# Upper_Board.net
KiCad netlist of a schematic drawn in EAGLE
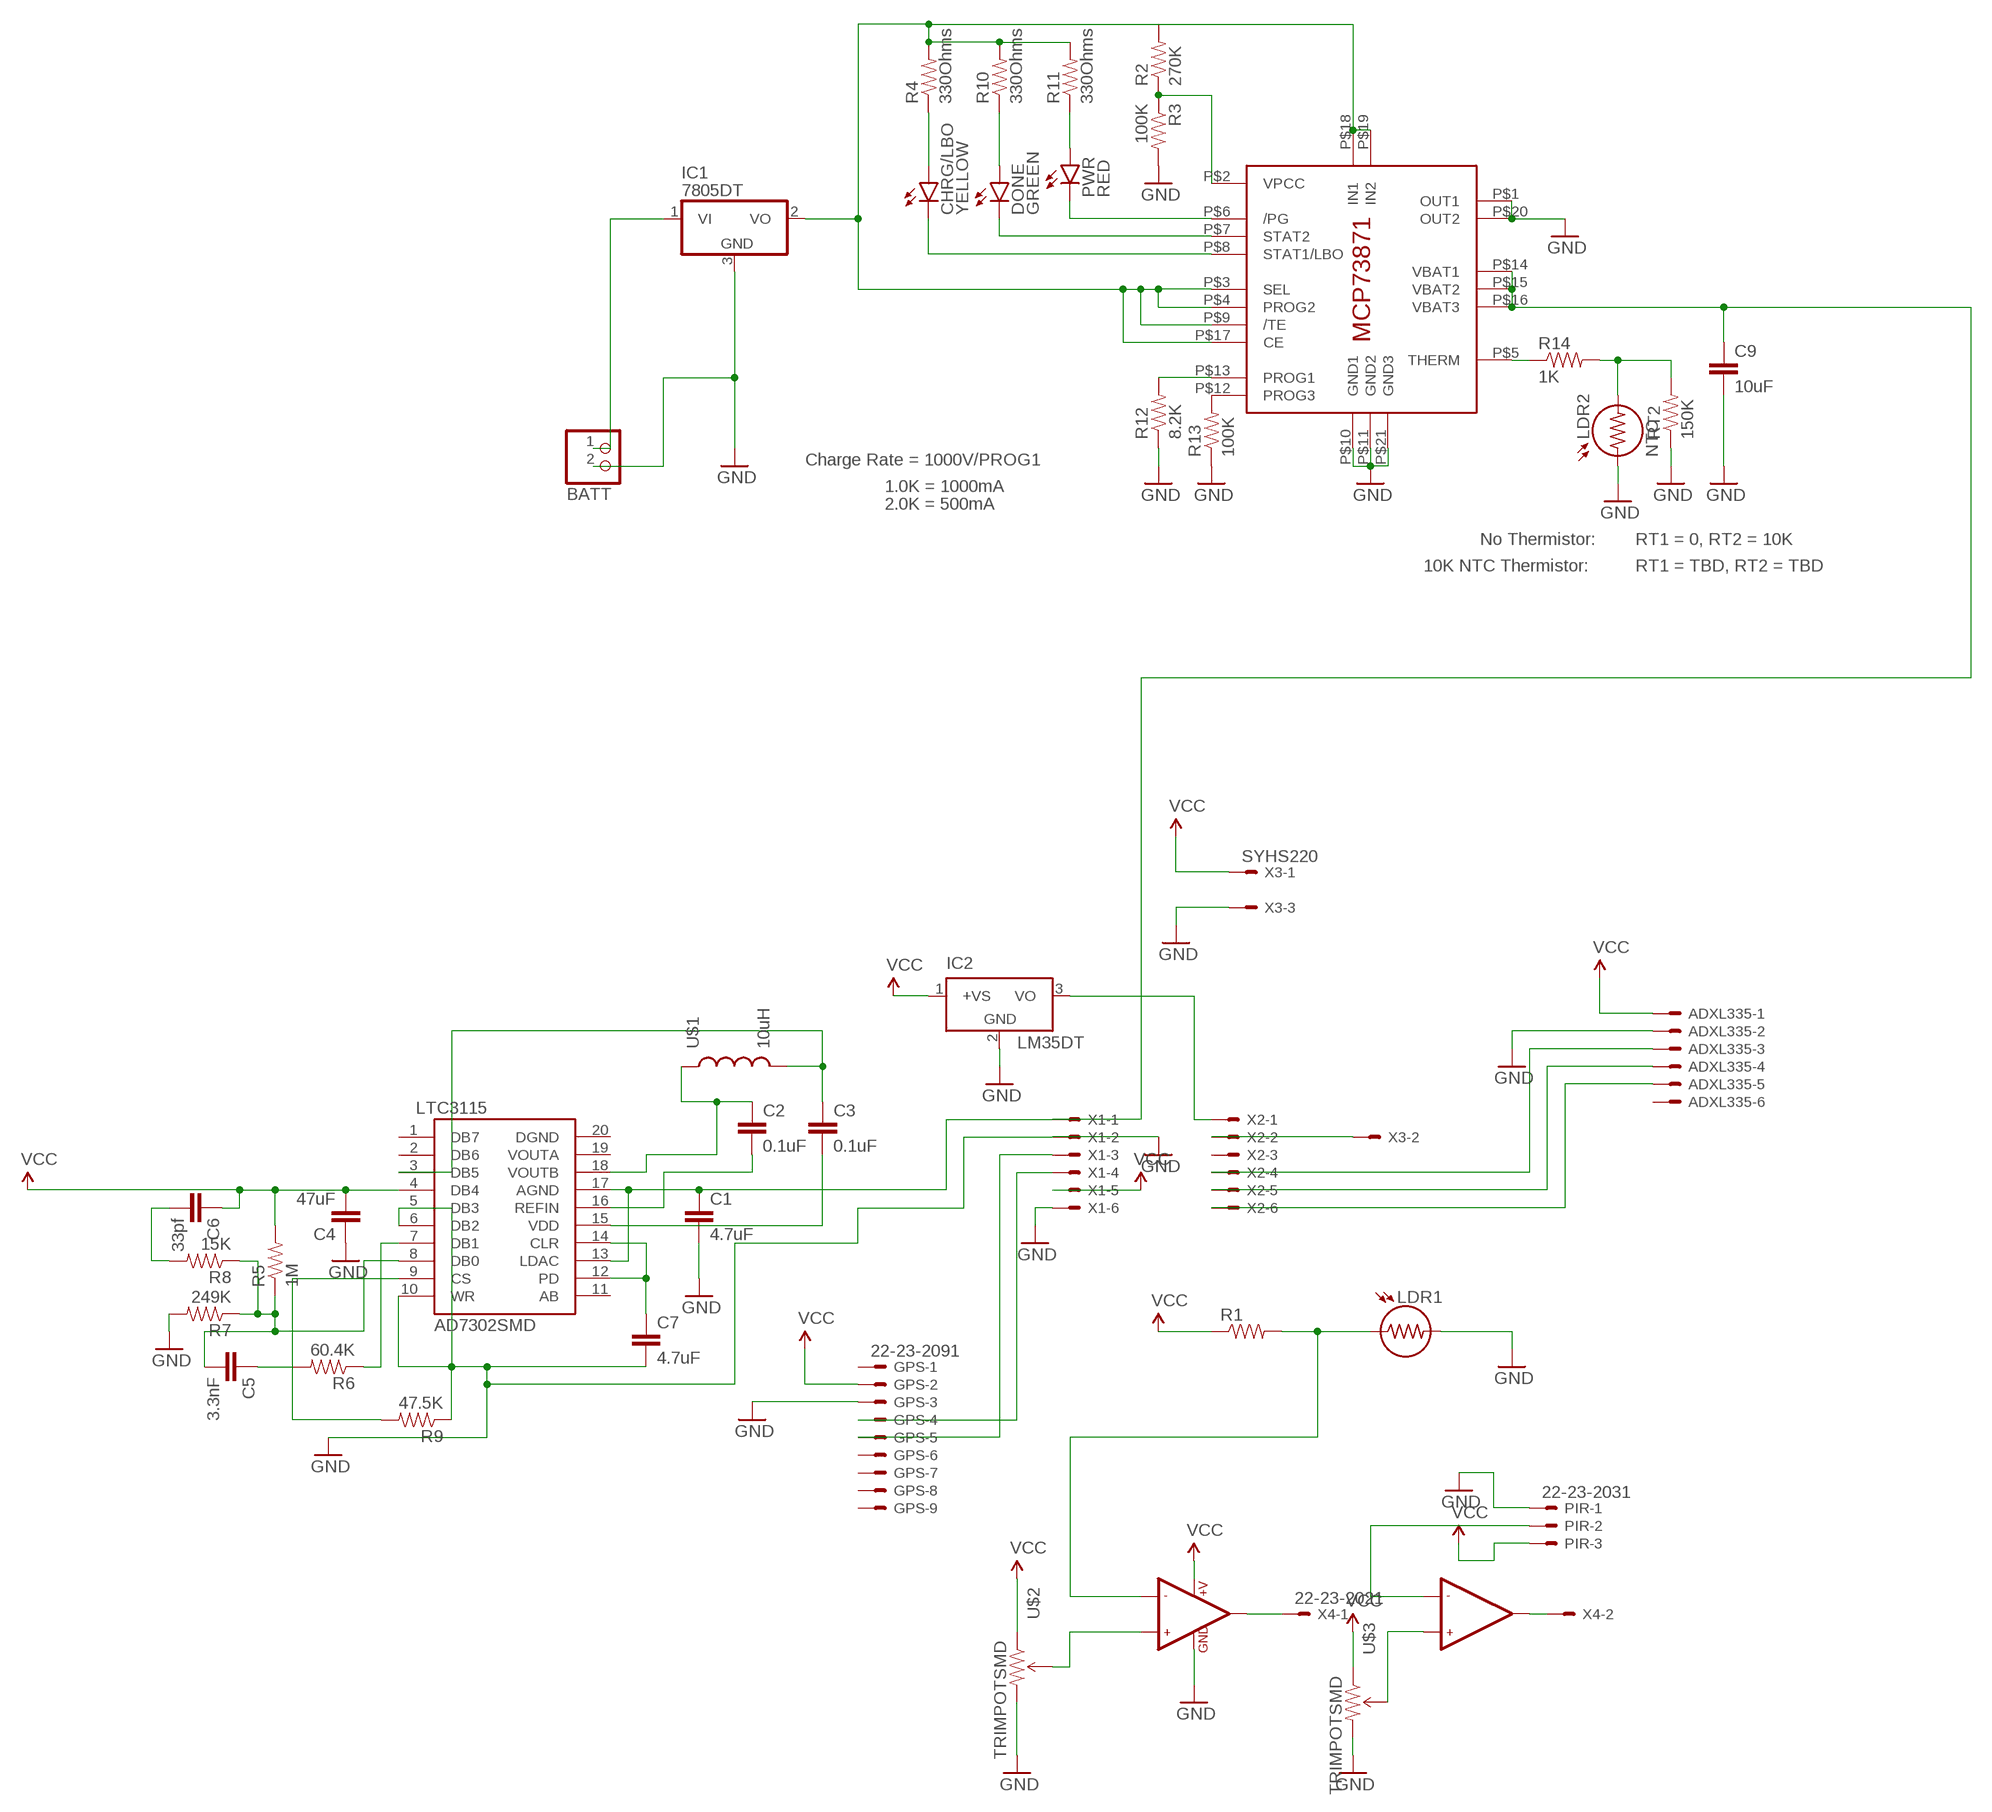
[diagram p0: schematic, sheet 1]

(export (version "E")
  (design (tool "Eeschema 10.0.6"))
  (components
    (comp (ref "ADXL335")
      (value "22-23-2061")
      (footprint "eagle-import:22-23-2061")
      (fields (field (name "MF") "MOLEX"))
      (libsource (lib "eagle-import") (part "22-23-2061"))
    )
    (comp (ref "BATT")
      (value "JST_2PIN-SMT-RA")
      (footprint "eagle-import:JST-PH-2-SMT-RA")
      (libsource (lib "eagle-import") (part "JST_2PIN-SMT-RA"))
    )
    (comp (ref "C1")
      (value "4.7uF")
      (footprint "eagle-import:0603-CAP")
      (libsource (lib "eagle-import") (part "CAP0603-CAP"))
    )
    (comp (ref "C2")
      (value "0.1uF")
      (footprint "eagle-import:0603-CAP")
      (libsource (lib "eagle-import") (part "CAP0603-CAP"))
    )
    (comp (ref "C3")
      (value "0.1uF")
      (footprint "eagle-import:0603-CAP")
      (libsource (lib "eagle-import") (part "CAP0603-CAP"))
    )
    (comp (ref "C4")
      (value "47uF")
      (footprint "eagle-import:0603-CAP")
      (libsource (lib "eagle-import") (part "CAP0603-CAP"))
    )
    (comp (ref "C5")
      (value "3.3nF")
      (footprint "eagle-import:0603-CAP")
      (libsource (lib "eagle-import") (part "CAP0603-CAP"))
    )
    (comp (ref "C6")
      (value "33pf")
      (footprint "eagle-import:0603-CAP")
      (libsource (lib "eagle-import") (part "CAP0603-CAP"))
    )
    (comp (ref "C7")
      (value "4.7uF")
      (footprint "eagle-import:0603-CAP")
      (libsource (lib "eagle-import") (part "CAP0603-CAP"))
    )
    (comp (ref "C9")
      (value "10uF")
      (footprint "eagle-import:0603-CAP")
      (libsource (lib "eagle-import") (part "CAP0603-CAP"))
    )
    (comp (ref "CHRG/LBO")
      (value "YELLOW")
      (footprint "eagle-import:LED-1206")
      (libsource (lib "eagle-import") (part "LED-YELLOWLARGE"))
    )
    (comp (ref "DONE")
      (value "GREEN")
      (footprint "eagle-import:LED-1206")
      (libsource (lib "eagle-import") (part "LED-GREENLARGE"))
    )
    (comp (ref "GPS")
      (value "22-23-2091")
      (footprint "eagle-import:22-23-2091")
      (fields (field (name "MF") "MOLEX"))
      (libsource (lib "eagle-import") (part "22-23-2091"))
    )
    (comp (ref "IC1")
      (value "7805DT")
      (footprint "eagle-import:TO252")
      (libsource (lib "eagle-import") (part "78DT05"))
    )
    (comp (ref "IC2")
      (value "LM35DT")
      (footprint "eagle-import:TO220V")
      (libsource (lib "eagle-import") (part "LM35DT"))
    )
    (comp (ref "IC4")
      (value "MCP73871")
      (footprint "eagle-import:QFN20_4MM")
      (libsource (lib "eagle-import") (part "MCP73871"))
    )
    (comp (ref "LDR1")
      (value "LDR5MM")
      (footprint "eagle-import:LDR338-54C")
      (libsource (lib "eagle-import") (part "LDR5MM"))
    )
    (comp (ref "LDR2")
      (value "NTC")
      (footprint "eagle-import:LDR338-54C")
      (libsource (lib "eagle-import") (part "LDR5MM"))
    )
    (comp (ref "LTC3115")
      (value "AD7302SMD")
      (footprint "eagle-import:TSSOP20")
      (libsource (lib "eagle-import") (part "AD7302SMD"))
    )
    (comp (ref "PIR")
      (value "22-23-2031")
      (footprint "eagle-import:22-23-2031")
      (fields (field (name "MF") "MOLEX"))
      (libsource (lib "eagle-import") (part "22-23-2031"))
    )
    (comp (ref "PWR")
      (value "RED")
      (footprint "eagle-import:LED-1206")
      (libsource (lib "eagle-import") (part "LED-RED1206"))
    )
    (comp (ref "R1")
      (value "RESISTOR1206")
      (footprint "eagle-import:1206")
      (libsource (lib "eagle-import") (part "RESISTOR1206"))
    )
    (comp (ref "R2")
      (value "270K")
      (footprint "eagle-import:1206")
      (libsource (lib "eagle-import") (part "RESISTOR1206"))
    )
    (comp (ref "R3")
      (value "100K")
      (footprint "eagle-import:1206")
      (libsource (lib "eagle-import") (part "RESISTOR1206"))
    )
    (comp (ref "R4")
      (value "330Ohms")
      (footprint "eagle-import:1206")
      (libsource (lib "eagle-import") (part "RESISTOR1206"))
    )
    (comp (ref "R5")
      (value "1M")
      (footprint "eagle-import:1206")
      (libsource (lib "eagle-import") (part "RESISTOR1206"))
    )
    (comp (ref "R6")
      (value "60.4K")
      (footprint "eagle-import:1206")
      (libsource (lib "eagle-import") (part "RESISTOR1206"))
    )
    (comp (ref "R7")
      (value "249K")
      (footprint "eagle-import:1206")
      (libsource (lib "eagle-import") (part "RESISTOR1206"))
    )
    (comp (ref "R8")
      (value "15K")
      (footprint "eagle-import:1206")
      (libsource (lib "eagle-import") (part "RESISTOR1206"))
    )
    (comp (ref "R9")
      (value "47.5K")
      (footprint "eagle-import:1206")
      (libsource (lib "eagle-import") (part "RESISTOR1206"))
    )
    (comp (ref "R10")
      (value "330Ohms")
      (footprint "eagle-import:1206")
      (libsource (lib "eagle-import") (part "RESISTOR1206"))
    )
    (comp (ref "R11")
      (value "330Ohms")
      (footprint "eagle-import:1206")
      (libsource (lib "eagle-import") (part "RESISTOR1206"))
    )
    (comp (ref "R12")
      (value "8.2K")
      (footprint "eagle-import:1206")
      (libsource (lib "eagle-import") (part "RESISTOR1206"))
    )
    (comp (ref "R13")
      (value "100K")
      (footprint "eagle-import:1206")
      (libsource (lib "eagle-import") (part "RESISTOR1206"))
    )
    (comp (ref "R14")
      (value "1K")
      (footprint "eagle-import:1206")
      (libsource (lib "eagle-import") (part "RESISTOR1206"))
    )
    (comp (ref "RT2")
      (value "150K")
      (footprint "eagle-import:1206")
      (libsource (lib "eagle-import") (part "RESISTOR1206"))
    )
    (comp (ref "U$1")
      (value "10uH")
      (footprint "eagle-import:INDUCTOR-1206")
      (libsource (lib "eagle-import") (part "INDUCTORH1206"))
    )
    (comp (ref "U$2")
      (value "TRIMPOTSMD")
      (footprint "eagle-import:TRIMPOT-3MM")
      (libsource (lib "eagle-import") (part "TRIMPOTSMD"))
    )
    (comp (ref "U$3")
      (value "TRIMPOTSMD")
      (footprint "eagle-import:TRIMPOT-3MM")
      (libsource (lib "eagle-import") (part "TRIMPOTSMD"))
    )
    (comp (ref "U$4")
      (value "LMV358")
      (footprint "eagle-import:SO08")
      (libsource (lib "eagle-import") (part "LMV358"))
    )
    (comp (ref "X1")
      (value "22-23-2061")
      (footprint "eagle-import:22-23-2061")
      (fields (field (name "MF") "MOLEX"))
      (libsource (lib "eagle-import") (part "22-23-2061"))
    )
    (comp (ref "X2")
      (value "22-23-2061")
      (footprint "eagle-import:22-23-2061")
      (fields (field (name "MF") "MOLEX"))
      (libsource (lib "eagle-import") (part "22-23-2061"))
    )
    (comp (ref "X3")
      (value "SYHS220")
      (footprint "eagle-import:22-23-2031")
      (fields (field (name "MF") "MOLEX") (field (name "MPN") "22-23-2031"))
      (libsource (lib "eagle-import") (part "22-23-2031"))
    )
    (comp (ref "X4")
      (value "22-23-2021")
      (footprint "eagle-import:22-23-2021")
      (fields (field (name "MF") "MOLEX"))
      (libsource (lib "eagle-import") (part "22-23-2021"))
    )
  )
  (nets
    (net (code "1") (name "GND") (class "Default")
      (node (ref "ADXL335") (pin "2") (pinfunction "S_2") (pintype "passive"))
      (node (ref "BATT") (pin "2") (pinfunction "1_2") (pintype "passive"))
      (node (ref "C1") (pin "2") (pinfunction "2_2") (pintype "passive"))
      (node (ref "C4") (pin "1") (pinfunction "1_1") (pintype "passive"))
      (node (ref "C7") (pin "2") (pinfunction "2_2") (pintype "passive"))
      (node (ref "C9") (pin "2") (pinfunction "2_2") (pintype "passive"))
      (node (ref "GPS") (pin "3") (pinfunction "S_3") (pintype "passive"))
      (node (ref "IC1") (pin "3") (pinfunction "GND_3") (pintype "passive"))
      (node (ref "IC2") (pin "2") (pinfunction "GND_2") (pintype "power_in"))
      (node (ref "IC4") (pin "P$1") (pinfunction "OUT1_P$1") (pintype "output"))
      (node (ref "IC4") (pin "P$10") (pinfunction "GND1_P$10") (pintype "power_in"))
      (node (ref "IC4") (pin "P$11") (pinfunction "GND2_P$11") (pintype "power_in"))
      (node (ref "IC4") (pin "P$20") (pinfunction "OUT2_P$20") (pintype "output"))
      (node (ref "IC4") (pin "P$21") (pinfunction "GND3_P$21") (pintype "power_in"))
      (node (ref "LDR1") (pin "2") (pinfunction "2_2") (pintype "passive"))
      (node (ref "LDR2") (pin "1") (pinfunction "1_1") (pintype "passive"))
      (node (ref "LTC3115") (pin "10") (pinfunction "WR_10") (pintype "bidirectional"))
      (node (ref "LTC3115") (pin "5") (pinfunction "DB3_5") (pintype "bidirectional"))
      (node (ref "LTC3115") (pin "6") (pinfunction "DB2_6") (pintype "bidirectional"))
      (node (ref "PIR") (pin "1") (pinfunction "S_1") (pintype "passive"))
      (node (ref "R12") (pin "1") (pinfunction "1_1") (pintype "passive"))
      (node (ref "R13") (pin "1") (pinfunction "1_1") (pintype "passive"))
      (node (ref "R3") (pin "2") (pinfunction "2_2") (pintype "passive"))
      (node (ref "R7") (pin "2") (pinfunction "2_2") (pintype "passive"))
      (node (ref "R9") (pin "1") (pinfunction "1_1") (pintype "passive"))
      (node (ref "RT2") (pin "1") (pinfunction "1_1") (pintype "passive"))
      (node (ref "U$2") (pin "3") (pinfunction "CW_3") (pintype "passive"))
      (node (ref "U$3") (pin "3") (pinfunction "CW_3") (pintype "passive"))
      (node (ref "U$4") (pin "4") (pinfunction "GND_4") (pintype "power_in"))
      (node (ref "X1") (pin "2") (pinfunction "S_2") (pintype "passive"))
      (node (ref "X1") (pin "6") (pinfunction "S_6") (pintype "passive"))
      (node (ref "X3") (pin "3") (pinfunction "S_3") (pintype "passive"))
    )
    (net (code "2") (name "Net-(ADXL335C-S)") (class "Default")
      (node (ref "ADXL335") (pin "3") (pinfunction "S_3") (pintype "passive"))
      (node (ref "X2") (pin "4") (pinfunction "S_4") (pintype "passive"))
    )
    (net (code "3") (name "Net-(ADXL335D-S)") (class "Default")
      (node (ref "ADXL335") (pin "4") (pinfunction "S_4") (pintype "passive"))
      (node (ref "X2") (pin "5") (pinfunction "S_5") (pintype "passive"))
    )
    (net (code "4") (name "Net-(ADXL335E-S)") (class "Default")
      (node (ref "ADXL335") (pin "5") (pinfunction "S_5") (pintype "passive"))
      (node (ref "X2") (pin "6") (pinfunction "S_6") (pintype "passive"))
    )
    (net (code "5") (name "Net-(BATT-2)") (class "Default")
      (node (ref "BATT") (pin "1") (pinfunction "2_1") (pintype "passive"))
      (node (ref "IC1") (pin "1") (pinfunction "VI_1") (pintype "input"))
    )
    (net (code "6") (name "Net-(C5-Pad1)") (class "Default")
      (node (ref "C5") (pin "1") (pinfunction "1_1") (pintype "passive"))
      (node (ref "R6") (pin "2") (pinfunction "2_2") (pintype "passive"))
    )
    (net (code "7") (name "Net-(C6-Pad2)") (class "Default")
      (node (ref "C6") (pin "2") (pinfunction "2_2") (pintype "passive"))
      (node (ref "R8") (pin "2") (pinfunction "2_2") (pintype "passive"))
    )
    (net (code "8") (name "Net-(CHRG/LBO-PadA)") (class "Default")
      (node (ref "CHRG/LBO") (pin "A") (pinfunction "A_A") (pintype "passive"))
      (node (ref "R4") (pin "1") (pinfunction "1_1") (pintype "passive"))
    )
    (net (code "9") (name "Net-(DONE-PadA)") (class "Default")
      (node (ref "DONE") (pin "A") (pinfunction "A_A") (pintype "passive"))
      (node (ref "R10") (pin "1") (pinfunction "1_1") (pintype "passive"))
    )
    (net (code "10") (name "Net-(GPSD-S)") (class "Default")
      (node (ref "GPS") (pin "4") (pinfunction "S_4") (pintype "passive"))
      (node (ref "X1") (pin "4") (pinfunction "S_4") (pintype "passive"))
    )
    (net (code "11") (name "Net-(GPSE-S)") (class "Default")
      (node (ref "GPS") (pin "5") (pinfunction "S_5") (pintype "passive"))
      (node (ref "X1") (pin "3") (pinfunction "S_3") (pintype "passive"))
    )
    (net (code "12") (name "Net-(IC1-VO)") (class "Default")
      (node (ref "IC1") (pin "2") (pinfunction "VO_2") (pintype "passive"))
      (node (ref "IC4") (pin "P$17") (pinfunction "CE_P$17") (pintype "input"))
      (node (ref "IC4") (pin "P$18") (pinfunction "IN1_P$18") (pintype "input"))
      (node (ref "IC4") (pin "P$19") (pinfunction "IN2_P$19") (pintype "input"))
      (node (ref "IC4") (pin "P$3") (pinfunction "SEL_P$3") (pintype "input"))
      (node (ref "IC4") (pin "P$4") (pinfunction "PROG2_P$4") (pintype "input"))
      (node (ref "IC4") (pin "P$9") (pinfunction "/TE_P$9") (pintype "input"))
      (node (ref "R10") (pin "2") (pinfunction "2_2") (pintype "passive"))
      (node (ref "R11") (pin "2") (pinfunction "2_2") (pintype "passive"))
      (node (ref "R2") (pin "2") (pinfunction "2_2") (pintype "passive"))
      (node (ref "R4") (pin "2") (pinfunction "2_2") (pintype "passive"))
    )
    (net (code "13") (name "Net-(IC2-VO)") (class "Default")
      (node (ref "IC2") (pin "3") (pinfunction "VO_3") (pintype "input"))
      (node (ref "X2") (pin "1") (pinfunction "S_1") (pintype "passive"))
    )
    (net (code "14") (name "Net-(IC4-PROG1)") (class "Default")
      (node (ref "IC4") (pin "P$13") (pinfunction "PROG1_P$13") (pintype "input"))
      (node (ref "R12") (pin "2") (pinfunction "2_2") (pintype "passive"))
    )
    (net (code "15") (name "Net-(IC4-PROG3)") (class "Default")
      (node (ref "IC4") (pin "P$12") (pinfunction "PROG3_P$12") (pintype "input"))
      (node (ref "R13") (pin "2") (pinfunction "2_2") (pintype "passive"))
    )
    (net (code "16") (name "Net-(IC4-STAT1{slash}LBO)") (class "Default")
      (node (ref "CHRG/LBO") (pin "C") (pinfunction "C_C") (pintype "passive"))
      (node (ref "IC4") (pin "P$8") (pinfunction "STAT1/LBO_P$8") (pintype "output"))
    )
    (net (code "17") (name "Net-(IC4-STAT2)") (class "Default")
      (node (ref "DONE") (pin "C") (pinfunction "C_C") (pintype "passive"))
      (node (ref "IC4") (pin "P$7") (pinfunction "STAT2_P$7") (pintype "output"))
    )
    (net (code "18") (name "Net-(IC4-THERM)") (class "Default")
      (node (ref "IC4") (pin "P$5") (pinfunction "THERM_P$5") (pintype "input"))
      (node (ref "R14") (pin "1") (pinfunction "1_1") (pintype "passive"))
    )
    (net (code "19") (name "Net-(IC4-VBAT1)") (class "Default")
      (node (ref "C1") (pin "1") (pinfunction "1_1") (pintype "passive"))
      (node (ref "C9") (pin "1") (pinfunction "1_1") (pintype "passive"))
      (node (ref "IC4") (pin "P$14") (pinfunction "VBAT1_P$14") (pintype "output"))
      (node (ref "IC4") (pin "P$15") (pinfunction "VBAT2_P$15") (pintype "output"))
      (node (ref "IC4") (pin "P$16") (pinfunction "VBAT3_P$16") (pintype "output"))
      (node (ref "LTC3115") (pin "13") (pinfunction "LDAC_13") (pintype "bidirectional"))
      (node (ref "LTC3115") (pin "17") (pinfunction "AGND_17") (pintype "bidirectional"))
      (node (ref "X1") (pin "1") (pinfunction "S_1") (pintype "passive"))
    )
    (net (code "20") (name "Net-(IC4-VPCC)") (class "Default")
      (node (ref "IC4") (pin "P$2") (pinfunction "VPCC_P$2") (pintype "input"))
      (node (ref "R2") (pin "1") (pinfunction "1_1") (pintype "passive"))
      (node (ref "R3") (pin "1") (pinfunction "1_1") (pintype "passive"))
    )
    (net (code "21") (name "Net-(IC4-{slash}PG)") (class "Default")
      (node (ref "IC4") (pin "P$6") (pinfunction "/PG_P$6") (pintype "output"))
      (node (ref "PWR") (pin "C") (pinfunction "C_C") (pintype "passive"))
    )
    (net (code "22") (name "Net-(LDR2-Pad2)") (class "Default")
      (node (ref "LDR2") (pin "2") (pinfunction "2_2") (pintype "passive"))
      (node (ref "R14") (pin "2") (pinfunction "2_2") (pintype "passive"))
      (node (ref "RT2") (pin "2") (pinfunction "2_2") (pintype "passive"))
    )
    (net (code "23") (name "Net-(LTC3115-CLR)") (class "Default")
      (node (ref "C7") (pin "1") (pinfunction "1_1") (pintype "passive"))
      (node (ref "LTC3115") (pin "12") (pinfunction "PD_12") (pintype "bidirectional"))
      (node (ref "LTC3115") (pin "14") (pinfunction "CLR_14") (pintype "bidirectional"))
    )
    (net (code "24") (name "Net-(LTC3115-CS)") (class "Default")
      (node (ref "LTC3115") (pin "9") (pinfunction "CS_9") (pintype "bidirectional"))
      (node (ref "R9") (pin "2") (pinfunction "2_2") (pintype "passive"))
    )
    (net (code "25") (name "Net-(LTC3115-DB0)") (class "Default")
      (node (ref "C5") (pin "2") (pinfunction "2_2") (pintype "passive"))
      (node (ref "LTC3115") (pin "8") (pinfunction "DB0_8") (pintype "bidirectional"))
      (node (ref "R5") (pin "1") (pinfunction "1_1") (pintype "passive"))
      (node (ref "R7") (pin "1") (pinfunction "1_1") (pintype "passive"))
      (node (ref "R8") (pin "1") (pinfunction "1_1") (pintype "passive"))
    )
    (net (code "26") (name "Net-(LTC3115-DB1)") (class "Default")
      (node (ref "LTC3115") (pin "7") (pinfunction "DB1_7") (pintype "bidirectional"))
      (node (ref "R6") (pin "1") (pinfunction "1_1") (pintype "passive"))
    )
    (net (code "27") (name "Net-(LTC3115-DB5)") (class "Default")
      (node (ref "C3") (pin "1") (pinfunction "1_1") (pintype "passive"))
      (node (ref "LTC3115") (pin "3") (pinfunction "DB5_3") (pintype "bidirectional"))
      (node (ref "U$1") (pin "P$2") (pinfunction "2_P$2") (pintype "passive"))
    )
    (net (code "28") (name "Net-(LTC3115-REFIN)") (class "Default")
      (node (ref "C2") (pin "2") (pinfunction "2_2") (pintype "passive"))
      (node (ref "LTC3115") (pin "16") (pinfunction "REFIN_16") (pintype "bidirectional"))
    )
    (net (code "29") (name "Net-(LTC3115-VDD)") (class "Default")
      (node (ref "C3") (pin "2") (pinfunction "2_2") (pintype "passive"))
      (node (ref "LTC3115") (pin "15") (pinfunction "VDD_15") (pintype "bidirectional"))
    )
    (net (code "30") (name "Net-(LTC3115-VOUTB)") (class "Default")
      (node (ref "C2") (pin "1") (pinfunction "1_1") (pintype "passive"))
      (node (ref "LTC3115") (pin "18") (pinfunction "VOUTB_18") (pintype "bidirectional"))
      (node (ref "U$1") (pin "P$1") (pinfunction "1_P$1") (pintype "passive"))
    )
    (net (code "31") (name "Net-(PIRB-S)") (class "Default")
      (node (ref "PIR") (pin "2") (pinfunction "S_2") (pintype "passive"))
      (node (ref "U$4") (pin "6") (pinfunction "-IN2_6") (pintype "input"))
    )
    (net (code "32") (name "Net-(PWR-PadA)") (class "Default")
      (node (ref "PWR") (pin "A") (pinfunction "A_A") (pintype "passive"))
      (node (ref "R11") (pin "1") (pinfunction "1_1") (pintype "passive"))
    )
    (net (code "33") (name "Net-(U$2-WIPER)") (class "Default")
      (node (ref "U$2") (pin "2") (pinfunction "WIPER_2") (pintype "passive"))
      (node (ref "U$4") (pin "3") (pinfunction "+IN1_3") (pintype "input"))
    )
    (net (code "34") (name "Net-(U$3-WIPER)") (class "Default")
      (node (ref "U$3") (pin "2") (pinfunction "WIPER_2") (pintype "passive"))
      (node (ref "U$4") (pin "5") (pinfunction "+IN2_5") (pintype "input"))
    )
    (net (code "35") (name "Net-(U$4A--IN1)") (class "Default")
      (node (ref "LDR1") (pin "1") (pinfunction "1_1") (pintype "passive"))
      (node (ref "R1") (pin "2") (pinfunction "2_2") (pintype "passive"))
      (node (ref "U$4") (pin "2") (pinfunction "-IN1_2") (pintype "input"))
    )
    (net (code "36") (name "Net-(U$4A-OUT1)") (class "Default")
      (node (ref "U$4") (pin "1") (pinfunction "OUT1_1") (pintype "output"))
      (node (ref "X4") (pin "1") (pinfunction "S_1") (pintype "passive"))
    )
    (net (code "37") (name "Net-(U$4B-OUT2)") (class "Default")
      (node (ref "U$4") (pin "7") (pinfunction "OUT2_7") (pintype "output"))
      (node (ref "X4") (pin "2") (pinfunction "S_2") (pintype "passive"))
    )
    (net (code "38") (name "Net-(X2B-S)") (class "Default")
      (node (ref "X2") (pin "2") (pinfunction "S_2") (pintype "passive"))
      (node (ref "X3") (pin "2") (pinfunction "S_2") (pintype "passive"))
    )
    (net (code "39") (name "VCC") (class "Default")
      (node (ref "ADXL335") (pin "1") (pinfunction "S_1") (pintype "passive"))
      (node (ref "C4") (pin "2") (pinfunction "2_2") (pintype "passive"))
      (node (ref "C6") (pin "1") (pinfunction "1_1") (pintype "passive"))
      (node (ref "GPS") (pin "2") (pinfunction "S_2") (pintype "passive"))
      (node (ref "IC2") (pin "1") (pinfunction "+VS_1") (pintype "input"))
      (node (ref "LTC3115") (pin "4") (pinfunction "DB4_4") (pintype "bidirectional"))
      (node (ref "PIR") (pin "3") (pinfunction "S_3") (pintype "passive"))
      (node (ref "R1") (pin "1") (pinfunction "1_1") (pintype "passive"))
      (node (ref "R5") (pin "2") (pinfunction "2_2") (pintype "passive"))
      (node (ref "U$2") (pin "1") (pinfunction "CCW_1") (pintype "passive"))
      (node (ref "U$3") (pin "1") (pinfunction "CCW_1") (pintype "passive"))
      (node (ref "U$4") (pin "8") (pinfunction "+V_8") (pintype "power_in"))
      (node (ref "X1") (pin "5") (pinfunction "S_5") (pintype "passive"))
      (node (ref "X3") (pin "1") (pinfunction "S_1") (pintype "passive"))
    )
    (net (code "40") (name "unconnected-(ADXL335F-S-Pad6)") (class "Default")
      (node (ref "ADXL335") (pin "6") (pinfunction "S_6") (pintype "passive"))
    )
    (net (code "41") (name "unconnected-(GPSA-S-Pad1)") (class "Default")
      (node (ref "GPS") (pin "1") (pinfunction "S_1") (pintype "passive"))
    )
    (net (code "42") (name "unconnected-(GPSF-S-Pad6)") (class "Default")
      (node (ref "GPS") (pin "6") (pinfunction "S_6") (pintype "passive"))
    )
    (net (code "43") (name "unconnected-(GPSG-S-Pad7)") (class "Default")
      (node (ref "GPS") (pin "7") (pinfunction "S_7") (pintype "passive"))
    )
    (net (code "44") (name "unconnected-(GPSH-S-Pad8)") (class "Default")
      (node (ref "GPS") (pin "8") (pinfunction "S_8") (pintype "passive"))
    )
    (net (code "45") (name "unconnected-(GPSI-S-Pad9)") (class "Default")
      (node (ref "GPS") (pin "9") (pinfunction "S_9") (pintype "passive"))
    )
    (net (code "46") (name "unconnected-(LTC3115-AB-Pad11)") (class "Default")
      (node (ref "LTC3115") (pin "11") (pinfunction "AB_11") (pintype "bidirectional"))
    )
    (net (code "47") (name "unconnected-(LTC3115-DB6-Pad2)") (class "Default")
      (node (ref "LTC3115") (pin "2") (pinfunction "DB6_2") (pintype "bidirectional"))
    )
    (net (code "48") (name "unconnected-(LTC3115-DB7-Pad1)") (class "Default")
      (node (ref "LTC3115") (pin "1") (pinfunction "DB7_1") (pintype "bidirectional"))
    )
    (net (code "49") (name "unconnected-(LTC3115-DGND-Pad20)") (class "Default")
      (node (ref "LTC3115") (pin "20") (pinfunction "DGND_20") (pintype "bidirectional"))
    )
    (net (code "50") (name "unconnected-(LTC3115-VOUTA-Pad19)") (class "Default")
      (node (ref "LTC3115") (pin "19") (pinfunction "VOUTA_19") (pintype "bidirectional"))
    )
    (net (code "51") (name "unconnected-(X2C-S-Pad3)") (class "Default")
      (node (ref "X2") (pin "3") (pinfunction "S_3") (pintype "passive"))
    )
  )
)
